# Spannungsversorgung_FinalVersion.net
KiCad netlist of a schematic drawn in EAGLE
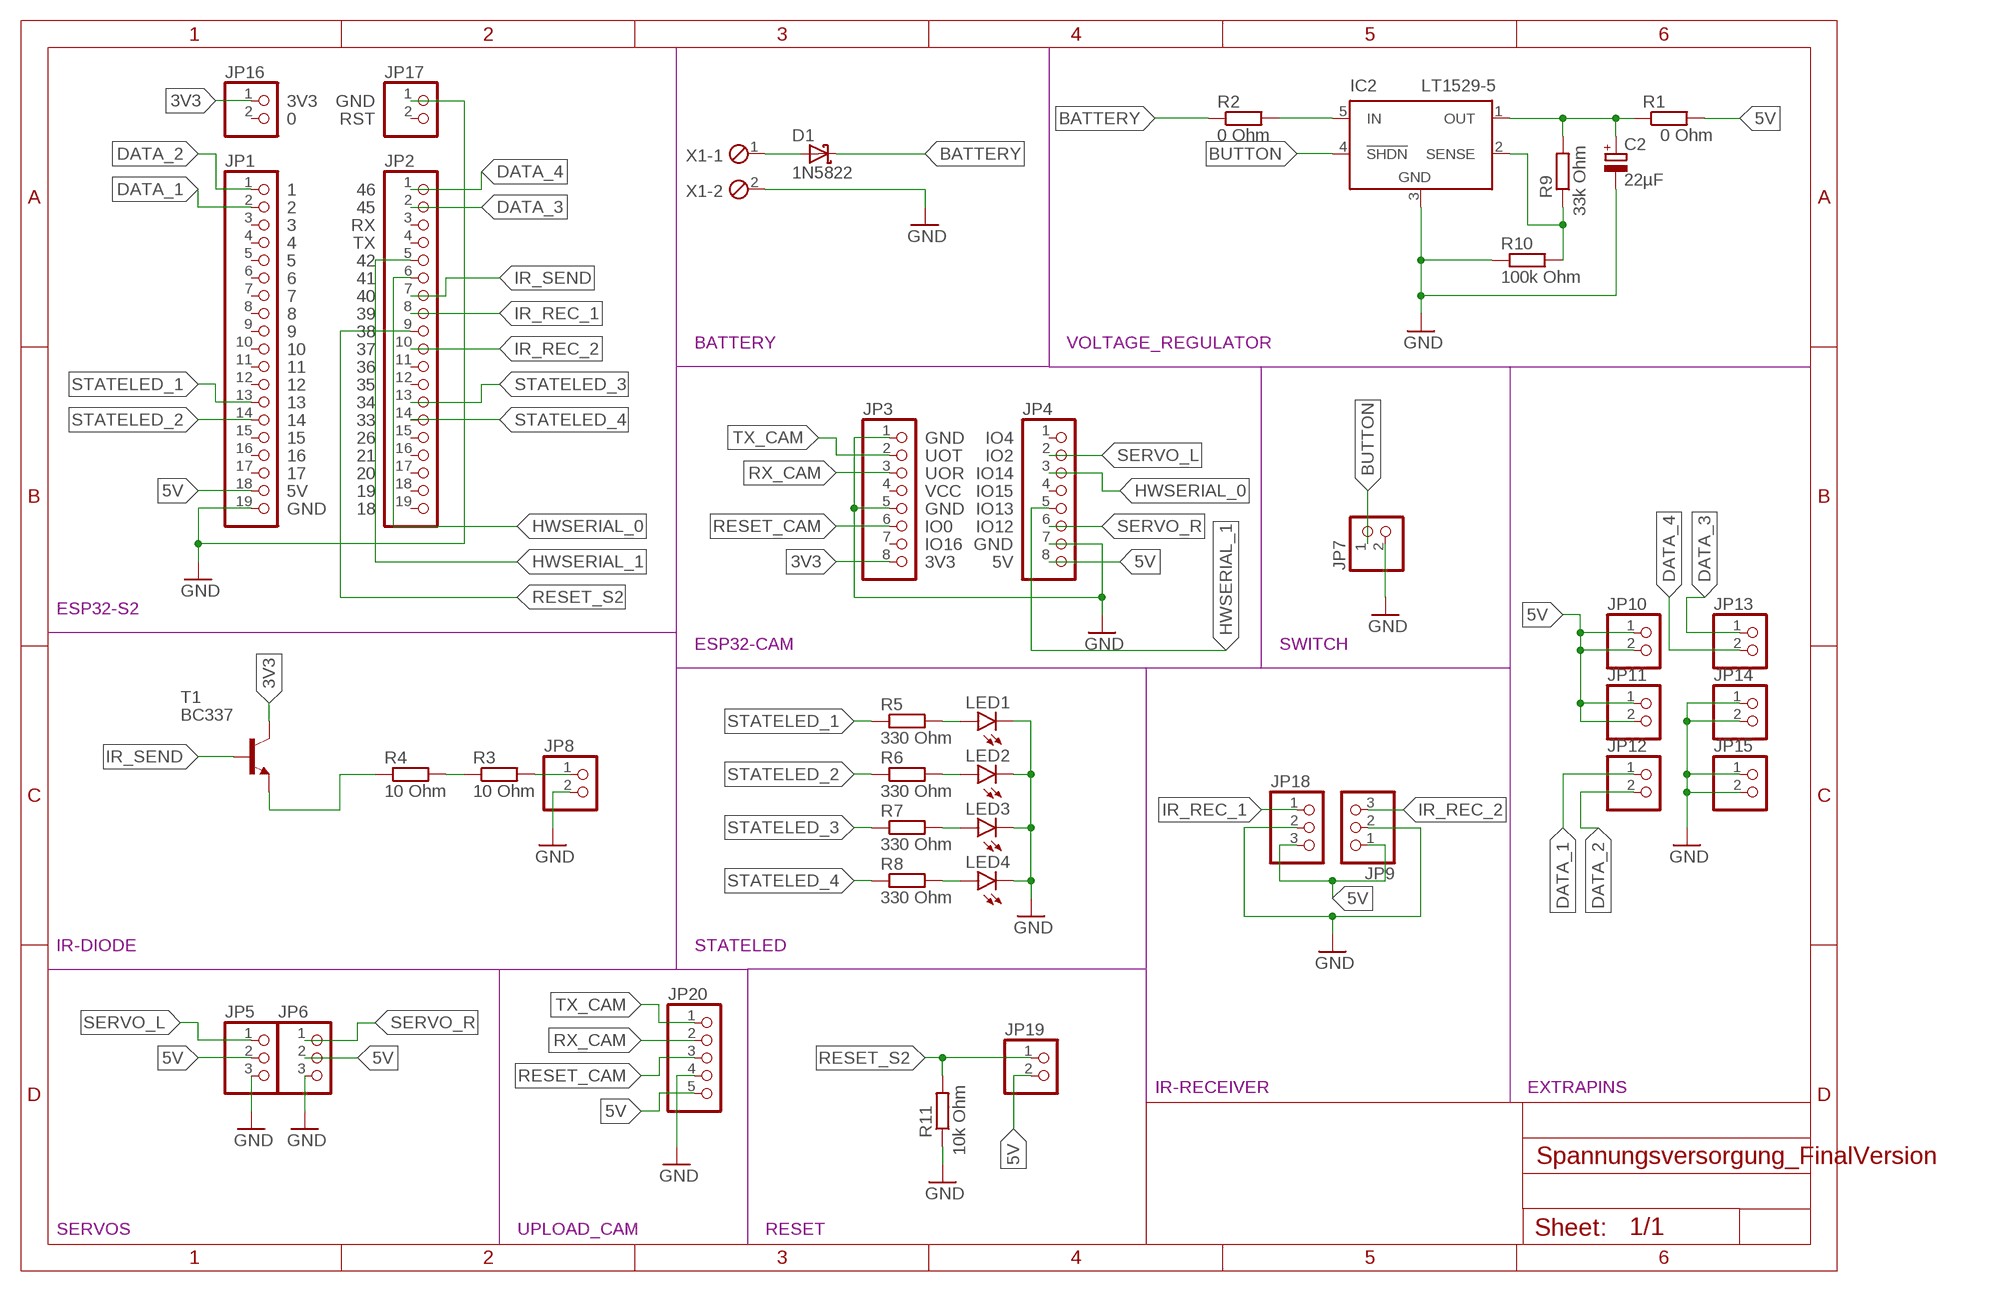
[diagram p0: schematic, sheet 1]

(export (version "E")
  (design (tool "Eeschema 10.0.6"))
  (components
    (comp (ref "C2")
      (value "22µF")
      (footprint "eagle-import:E2,5-5")
      (libsource (lib "eagle-import") (part "CPOL-EUE2.5-5"))
    )
    (comp (ref "D1")
      (value "1N5822")
      (footprint "eagle-import:DIOAD2120W130L950D530P")
      (fields (field (name "MF") "ON Semiconductor"))
      (libsource (lib "eagle-import") (part "1N5822"))
    )
    (comp (ref "IC2")
      (value "LT1529-5")
      (footprint "eagle-import:TO220-5")
      (libsource (lib "eagle-import") (part "LT1529T"))
    )
    (comp (ref "JP1")
      (value "PINHD-1X19")
      (footprint "eagle-import:1X19")
      (libsource (lib "eagle-import") (part "PINHD-1X19"))
    )
    (comp (ref "JP2")
      (value "PINHD-1X19")
      (footprint "eagle-import:1X19")
      (libsource (lib "eagle-import") (part "PINHD-1X19"))
    )
    (comp (ref "JP3")
      (value "PINHD-1X8")
      (footprint "eagle-import:1X08")
      (libsource (lib "eagle-import") (part "PINHD-1X8"))
    )
    (comp (ref "JP4")
      (value "PINHD-1X8")
      (footprint "eagle-import:1X08")
      (libsource (lib "eagle-import") (part "PINHD-1X8"))
    )
    (comp (ref "JP5")
      (value "PINHD-1X3")
      (footprint "eagle-import:1X03")
      (libsource (lib "eagle-import") (part "PINHD-1X3"))
    )
    (comp (ref "JP6")
      (value "PINHD-1X3")
      (footprint "eagle-import:1X03")
      (libsource (lib "eagle-import") (part "PINHD-1X3"))
    )
    (comp (ref "JP7")
      (value "PINHD-1X2")
      (footprint "eagle-import:1X02")
      (libsource (lib "eagle-import") (part "PINHD-1X2"))
    )
    (comp (ref "JP8")
      (value "PINHD-1X2")
      (footprint "eagle-import:1X02")
      (libsource (lib "eagle-import") (part "PINHD-1X2"))
    )
    (comp (ref "JP9")
      (value "PINHD-1X3")
      (footprint "eagle-import:1X03")
      (libsource (lib "eagle-import") (part "PINHD-1X3"))
    )
    (comp (ref "JP10")
      (value "PINHD-1X2")
      (footprint "eagle-import:1X02")
      (libsource (lib "eagle-import") (part "PINHD-1X2"))
    )
    (comp (ref "JP11")
      (value "PINHD-1X2")
      (footprint "eagle-import:1X02")
      (libsource (lib "eagle-import") (part "PINHD-1X2"))
    )
    (comp (ref "JP12")
      (value "PINHD-1X2")
      (footprint "eagle-import:1X02")
      (libsource (lib "eagle-import") (part "PINHD-1X2"))
    )
    (comp (ref "JP13")
      (value "PINHD-1X2")
      (footprint "eagle-import:1X02")
      (libsource (lib "eagle-import") (part "PINHD-1X2"))
    )
    (comp (ref "JP14")
      (value "PINHD-1X2")
      (footprint "eagle-import:1X02")
      (libsource (lib "eagle-import") (part "PINHD-1X2"))
    )
    (comp (ref "JP15")
      (value "PINHD-1X2")
      (footprint "eagle-import:1X02")
      (libsource (lib "eagle-import") (part "PINHD-1X2"))
    )
    (comp (ref "JP16")
      (value "PINHD-1X2")
      (footprint "eagle-import:1X02")
      (libsource (lib "eagle-import") (part "PINHD-1X2"))
    )
    (comp (ref "JP17")
      (value "PINHD-1X2")
      (footprint "eagle-import:1X02")
      (libsource (lib "eagle-import") (part "PINHD-1X2"))
    )
    (comp (ref "JP18")
      (value "PINHD-1X3")
      (footprint "eagle-import:1X03")
      (libsource (lib "eagle-import") (part "PINHD-1X3"))
    )
    (comp (ref "JP19")
      (value "PINHD-1X2")
      (footprint "eagle-import:1X02")
      (libsource (lib "eagle-import") (part "PINHD-1X2"))
    )
    (comp (ref "JP20")
      (value "PINHD-1X5")
      (footprint "eagle-import:1X05")
      (libsource (lib "eagle-import") (part "PINHD-1X5"))
    )
    (comp (ref "LED1")
      (value "LED3MM")
      (footprint "eagle-import:LED3MM")
      (libsource (lib "eagle-import") (part "LED3MM"))
    )
    (comp (ref "LED2")
      (value "LED3MM")
      (footprint "eagle-import:LED3MM")
      (libsource (lib "eagle-import") (part "LED3MM"))
    )
    (comp (ref "LED3")
      (value "LED3MM")
      (footprint "eagle-import:LED3MM")
      (libsource (lib "eagle-import") (part "LED3MM"))
    )
    (comp (ref "LED4")
      (value "LED3MM")
      (footprint "eagle-import:LED3MM")
      (libsource (lib "eagle-import") (part "LED3MM"))
    )
    (comp (ref "R1")
      (value "0 Ohm")
      (footprint "eagle-import:R0805")
      (libsource (lib "eagle-import") (part "R-EU_R0805"))
    )
    (comp (ref "R2")
      (value "0 Ohm")
      (footprint "eagle-import:R0805")
      (libsource (lib "eagle-import") (part "R-EU_R0805"))
    )
    (comp (ref "R3")
      (value "10 Ohm")
      (footprint "eagle-import:0309_12")
      (libsource (lib "eagle-import") (part "R-EU_0309/12"))
    )
    (comp (ref "R4")
      (value "10 Ohm")
      (footprint "eagle-import:0309_12")
      (libsource (lib "eagle-import") (part "R-EU_0309/12"))
    )
    (comp (ref "R5")
      (value "330 Ohm")
      (footprint "eagle-import:R0805")
      (libsource (lib "eagle-import") (part "R-EU_R0805"))
    )
    (comp (ref "R6")
      (value "330 Ohm")
      (footprint "eagle-import:R0805")
      (libsource (lib "eagle-import") (part "R-EU_R0805"))
    )
    (comp (ref "R7")
      (value "330 Ohm")
      (footprint "eagle-import:R0805")
      (libsource (lib "eagle-import") (part "R-EU_R0805"))
    )
    (comp (ref "R8")
      (value "330 Ohm")
      (footprint "eagle-import:R0805")
      (libsource (lib "eagle-import") (part "R-EU_R0805"))
    )
    (comp (ref "R9")
      (value "33k Ohm")
      (footprint "eagle-import:0309_12")
      (libsource (lib "eagle-import") (part "R-EU_0309/12"))
    )
    (comp (ref "R10")
      (value "100k Ohm")
      (footprint "eagle-import:0309_12")
      (libsource (lib "eagle-import") (part "R-EU_0309/12"))
    )
    (comp (ref "R11")
      (value "10k Ohm")
      (footprint "eagle-import:0309_12")
      (libsource (lib "eagle-import") (part "R-EU_0309/12"))
    )
    (comp (ref "T1")
      (value "BC337")
      (footprint "eagle-import:TO92")
      (libsource (lib "eagle-import") (part "BC337"))
    )
    (comp (ref "X1")
      (value "MPT2")
      (footprint "eagle-import:2POL254")
      (libsource (lib "eagle-import") (part "MPT2"))
    )
  )
  (nets
    (net (code "1") (name "3V3") (class "Default")
      (node (ref "JP16") (pin "1") (pinfunction "1_1") (pintype "passive"))
      (node (ref "JP3") (pin "8") (pinfunction "8_8") (pintype "passive"))
      (node (ref "T1") (pin "3") (pinfunction "C_3") (pintype "passive"))
    )
    (net (code "2") (name "5V") (class "Default")
      (node (ref "JP1") (pin "18") (pinfunction "18_18") (pintype "passive"))
      (node (ref "JP10") (pin "1") (pinfunction "1_1") (pintype "passive"))
      (node (ref "JP10") (pin "2") (pinfunction "2_2") (pintype "passive"))
      (node (ref "JP11") (pin "1") (pinfunction "1_1") (pintype "passive"))
      (node (ref "JP11") (pin "2") (pinfunction "2_2") (pintype "passive"))
      (node (ref "JP18") (pin "3") (pinfunction "3_3") (pintype "passive"))
      (node (ref "JP19") (pin "2") (pinfunction "2_2") (pintype "passive"))
      (node (ref "JP20") (pin "5") (pinfunction "5_5") (pintype "passive"))
      (node (ref "JP4") (pin "8") (pinfunction "8_8") (pintype "passive"))
      (node (ref "JP5") (pin "2") (pinfunction "2_2") (pintype "passive"))
      (node (ref "JP6") (pin "2") (pinfunction "2_2") (pintype "passive"))
      (node (ref "JP9") (pin "1") (pinfunction "1_1") (pintype "passive"))
      (node (ref "R1") (pin "2") (pinfunction "2_2") (pintype "passive"))
    )
    (net (code "3") (name "BATTERY") (class "Default")
      (node (ref "D1") (pin "C") (pinfunction "C_C") (pintype "passive"))
      (node (ref "R2") (pin "1") (pinfunction "1_1") (pintype "passive"))
    )
    (net (code "4") (name "BUTTON") (class "Default")
      (node (ref "IC2") (pin "4") (pinfunction "~{SHDN}_4") (pintype "input"))
      (node (ref "JP7") (pin "1") (pinfunction "1_1") (pintype "passive"))
    )
    (net (code "5") (name "DATA_1") (class "Default")
      (node (ref "JP1") (pin "2") (pinfunction "2_2") (pintype "passive"))
      (node (ref "JP12") (pin "1") (pinfunction "1_1") (pintype "passive"))
    )
    (net (code "6") (name "DATA_2") (class "Default")
      (node (ref "JP1") (pin "1") (pinfunction "1_1") (pintype "passive"))
      (node (ref "JP12") (pin "2") (pinfunction "2_2") (pintype "passive"))
    )
    (net (code "7") (name "DATA_3") (class "Default")
      (node (ref "JP13") (pin "1") (pinfunction "1_1") (pintype "passive"))
      (node (ref "JP2") (pin "2") (pinfunction "2_2") (pintype "passive"))
    )
    (net (code "8") (name "DATA_4") (class "Default")
      (node (ref "JP13") (pin "2") (pinfunction "2_2") (pintype "passive"))
      (node (ref "JP2") (pin "1") (pinfunction "1_1") (pintype "passive"))
    )
    (net (code "9") (name "GND") (class "Default")
      (node (ref "C2") (pin "-") (pinfunction "-_-") (pintype "passive"))
      (node (ref "IC2") (pin "3") (pinfunction "GND_3") (pintype "power_in"))
      (node (ref "JP1") (pin "19") (pinfunction "19_19") (pintype "passive"))
      (node (ref "JP14") (pin "1") (pinfunction "1_1") (pintype "passive"))
      (node (ref "JP14") (pin "2") (pinfunction "2_2") (pintype "passive"))
      (node (ref "JP15") (pin "1") (pinfunction "1_1") (pintype "passive"))
      (node (ref "JP15") (pin "2") (pinfunction "2_2") (pintype "passive"))
      (node (ref "JP17") (pin "1") (pinfunction "1_1") (pintype "passive"))
      (node (ref "JP18") (pin "2") (pinfunction "2_2") (pintype "passive"))
      (node (ref "JP20") (pin "4") (pinfunction "4_4") (pintype "passive"))
      (node (ref "JP3") (pin "1") (pinfunction "1_1") (pintype "passive"))
      (node (ref "JP3") (pin "5") (pinfunction "5_5") (pintype "passive"))
      (node (ref "JP4") (pin "7") (pinfunction "7_7") (pintype "passive"))
      (node (ref "JP5") (pin "3") (pinfunction "3_3") (pintype "passive"))
      (node (ref "JP6") (pin "3") (pinfunction "3_3") (pintype "passive"))
      (node (ref "JP7") (pin "2") (pinfunction "2_2") (pintype "passive"))
      (node (ref "JP8") (pin "2") (pinfunction "2_2") (pintype "passive"))
      (node (ref "JP9") (pin "2") (pinfunction "2_2") (pintype "passive"))
      (node (ref "LED1") (pin "K") (pinfunction "C_K") (pintype "passive"))
      (node (ref "LED2") (pin "K") (pinfunction "C_K") (pintype "passive"))
      (node (ref "LED3") (pin "K") (pinfunction "C_K") (pintype "passive"))
      (node (ref "LED4") (pin "K") (pinfunction "C_K") (pintype "passive"))
      (node (ref "R10") (pin "1") (pinfunction "1_1") (pintype "passive"))
      (node (ref "R11") (pin "1") (pinfunction "1_1") (pintype "passive"))
      (node (ref "X1") (pin "2") (pinfunction "1_2") (pintype "passive"))
    )
    (net (code "10") (name "HWSERIAL_0") (class "Default")
      (node (ref "JP2") (pin "6") (pinfunction "6_6") (pintype "passive"))
      (node (ref "JP4") (pin "3") (pinfunction "3_3") (pintype "passive"))
    )
    (net (code "11") (name "HWSERIAL_1") (class "Default")
      (node (ref "JP2") (pin "5") (pinfunction "5_5") (pintype "passive"))
      (node (ref "JP4") (pin "5") (pinfunction "5_5") (pintype "passive"))
    )
    (net (code "12") (name "IR_REC_1") (class "Default")
      (node (ref "JP18") (pin "1") (pinfunction "1_1") (pintype "passive"))
      (node (ref "JP2") (pin "8") (pinfunction "8_8") (pintype "passive"))
    )
    (net (code "13") (name "IR_REC_2") (class "Default")
      (node (ref "JP2") (pin "10") (pinfunction "10_10") (pintype "passive"))
      (node (ref "JP9") (pin "3") (pinfunction "3_3") (pintype "passive"))
    )
    (net (code "14") (name "IR_SEND") (class "Default")
      (node (ref "JP2") (pin "7") (pinfunction "7_7") (pintype "passive"))
      (node (ref "T1") (pin "2") (pinfunction "B_2") (pintype "passive"))
    )
    (net (code "15") (name "Net-(D1-PadA)") (class "Default")
      (node (ref "D1") (pin "A") (pinfunction "A_A") (pintype "passive"))
      (node (ref "X1") (pin "1") (pinfunction "1_1") (pintype "passive"))
    )
    (net (code "16") (name "Net-(IC2-IN)") (class "Default")
      (node (ref "IC2") (pin "5") (pinfunction "IN_5") (pintype "input"))
      (node (ref "R2") (pin "2") (pinfunction "2_2") (pintype "passive"))
    )
    (net (code "17") (name "Net-(IC2-OUT)") (class "Default")
      (node (ref "C2") (pin "+") (pinfunction "+_+") (pintype "passive"))
      (node (ref "IC2") (pin "1") (pinfunction "OUT_1") (pintype "output"))
      (node (ref "R1") (pin "1") (pinfunction "1_1") (pintype "passive"))
      (node (ref "R9") (pin "2") (pinfunction "2_2") (pintype "passive"))
    )
    (net (code "18") (name "Net-(IC2-SENSE)") (class "Default")
      (node (ref "IC2") (pin "2") (pinfunction "SENSE_2") (pintype "input"))
      (node (ref "R10") (pin "2") (pinfunction "2_2") (pintype "passive"))
      (node (ref "R9") (pin "1") (pinfunction "1_1") (pintype "passive"))
    )
    (net (code "19") (name "Net-(JP8-Pad1)") (class "Default")
      (node (ref "JP8") (pin "1") (pinfunction "1_1") (pintype "passive"))
      (node (ref "R3") (pin "2") (pinfunction "2_2") (pintype "passive"))
    )
    (net (code "20") (name "Net-(LED1-PadA)") (class "Default")
      (node (ref "LED1") (pin "A") (pinfunction "A_A") (pintype "passive"))
      (node (ref "R5") (pin "2") (pinfunction "2_2") (pintype "passive"))
    )
    (net (code "21") (name "Net-(LED2-PadA)") (class "Default")
      (node (ref "LED2") (pin "A") (pinfunction "A_A") (pintype "passive"))
      (node (ref "R6") (pin "2") (pinfunction "2_2") (pintype "passive"))
    )
    (net (code "22") (name "Net-(LED3-PadA)") (class "Default")
      (node (ref "LED3") (pin "A") (pinfunction "A_A") (pintype "passive"))
      (node (ref "R7") (pin "2") (pinfunction "2_2") (pintype "passive"))
    )
    (net (code "23") (name "Net-(LED4-PadA)") (class "Default")
      (node (ref "LED4") (pin "A") (pinfunction "A_A") (pintype "passive"))
      (node (ref "R8") (pin "2") (pinfunction "2_2") (pintype "passive"))
    )
    (net (code "24") (name "Net-(R3-Pad1)") (class "Default")
      (node (ref "R3") (pin "1") (pinfunction "1_1") (pintype "passive"))
      (node (ref "R4") (pin "2") (pinfunction "2_2") (pintype "passive"))
    )
    (net (code "25") (name "Net-(T1-E)") (class "Default")
      (node (ref "R4") (pin "1") (pinfunction "1_1") (pintype "passive"))
      (node (ref "T1") (pin "1") (pinfunction "E_1") (pintype "passive"))
    )
    (net (code "26") (name "RESET_CAM") (class "Default")
      (node (ref "JP20") (pin "3") (pinfunction "3_3") (pintype "passive"))
      (node (ref "JP3") (pin "6") (pinfunction "6_6") (pintype "passive"))
    )
    (net (code "27") (name "RESET_S2") (class "Default")
      (node (ref "JP19") (pin "1") (pinfunction "1_1") (pintype "passive"))
      (node (ref "JP2") (pin "9") (pinfunction "9_9") (pintype "passive"))
      (node (ref "R11") (pin "2") (pinfunction "2_2") (pintype "passive"))
    )
    (net (code "28") (name "RX_CAM") (class "Default")
      (node (ref "JP20") (pin "2") (pinfunction "2_2") (pintype "passive"))
      (node (ref "JP3") (pin "3") (pinfunction "3_3") (pintype "passive"))
    )
    (net (code "29") (name "SERVO_L") (class "Default")
      (node (ref "JP4") (pin "2") (pinfunction "2_2") (pintype "passive"))
      (node (ref "JP5") (pin "1") (pinfunction "1_1") (pintype "passive"))
    )
    (net (code "30") (name "SERVO_R") (class "Default")
      (node (ref "JP4") (pin "6") (pinfunction "6_6") (pintype "passive"))
      (node (ref "JP6") (pin "1") (pinfunction "1_1") (pintype "passive"))
    )
    (net (code "31") (name "STATELED_1") (class "Default")
      (node (ref "JP1") (pin "13") (pinfunction "13_13") (pintype "passive"))
      (node (ref "R5") (pin "1") (pinfunction "1_1") (pintype "passive"))
    )
    (net (code "32") (name "STATELED_2") (class "Default")
      (node (ref "JP1") (pin "14") (pinfunction "14_14") (pintype "passive"))
      (node (ref "R6") (pin "1") (pinfunction "1_1") (pintype "passive"))
    )
    (net (code "33") (name "STATELED_3") (class "Default")
      (node (ref "JP2") (pin "13") (pinfunction "13_13") (pintype "passive"))
      (node (ref "R7") (pin "1") (pinfunction "1_1") (pintype "passive"))
    )
    (net (code "34") (name "STATELED_4") (class "Default")
      (node (ref "JP2") (pin "14") (pinfunction "14_14") (pintype "passive"))
      (node (ref "R8") (pin "1") (pinfunction "1_1") (pintype "passive"))
    )
    (net (code "35") (name "TX_CAM") (class "Default")
      (node (ref "JP20") (pin "1") (pinfunction "1_1") (pintype "passive"))
      (node (ref "JP3") (pin "2") (pinfunction "2_2") (pintype "passive"))
    )
    (net (code "36") (name "unconnected-(JP1-Pad3)") (class "Default")
      (node (ref "JP1") (pin "3") (pinfunction "3_3") (pintype "passive"))
    )
    (net (code "37") (name "unconnected-(JP1-Pad4)") (class "Default")
      (node (ref "JP1") (pin "4") (pinfunction "4_4") (pintype "passive"))
    )
    (net (code "38") (name "unconnected-(JP1-Pad5)") (class "Default")
      (node (ref "JP1") (pin "5") (pinfunction "5_5") (pintype "passive"))
    )
    (net (code "39") (name "unconnected-(JP1-Pad6)") (class "Default")
      (node (ref "JP1") (pin "6") (pinfunction "6_6") (pintype "passive"))
    )
    (net (code "40") (name "unconnected-(JP1-Pad7)") (class "Default")
      (node (ref "JP1") (pin "7") (pinfunction "7_7") (pintype "passive"))
    )
    (net (code "41") (name "unconnected-(JP1-Pad8)") (class "Default")
      (node (ref "JP1") (pin "8") (pinfunction "8_8") (pintype "passive"))
    )
    (net (code "42") (name "unconnected-(JP1-Pad9)") (class "Default")
      (node (ref "JP1") (pin "9") (pinfunction "9_9") (pintype "passive"))
    )
    (net (code "43") (name "unconnected-(JP1-Pad10)") (class "Default")
      (node (ref "JP1") (pin "10") (pinfunction "10_10") (pintype "passive"))
    )
    (net (code "44") (name "unconnected-(JP1-Pad11)") (class "Default")
      (node (ref "JP1") (pin "11") (pinfunction "11_11") (pintype "passive"))
    )
    (net (code "45") (name "unconnected-(JP1-Pad12)") (class "Default")
      (node (ref "JP1") (pin "12") (pinfunction "12_12") (pintype "passive"))
    )
    (net (code "46") (name "unconnected-(JP1-Pad15)") (class "Default")
      (node (ref "JP1") (pin "15") (pinfunction "15_15") (pintype "passive"))
    )
    (net (code "47") (name "unconnected-(JP1-Pad16)") (class "Default")
      (node (ref "JP1") (pin "16") (pinfunction "16_16") (pintype "passive"))
    )
    (net (code "48") (name "unconnected-(JP1-Pad17)") (class "Default")
      (node (ref "JP1") (pin "17") (pinfunction "17_17") (pintype "passive"))
    )
    (net (code "49") (name "unconnected-(JP2-Pad3)") (class "Default")
      (node (ref "JP2") (pin "3") (pinfunction "3_3") (pintype "passive"))
    )
    (net (code "50") (name "unconnected-(JP2-Pad4)") (class "Default")
      (node (ref "JP2") (pin "4") (pinfunction "4_4") (pintype "passive"))
    )
    (net (code "51") (name "unconnected-(JP2-Pad11)") (class "Default")
      (node (ref "JP2") (pin "11") (pinfunction "11_11") (pintype "passive"))
    )
    (net (code "52") (name "unconnected-(JP2-Pad12)") (class "Default")
      (node (ref "JP2") (pin "12") (pinfunction "12_12") (pintype "passive"))
    )
    (net (code "53") (name "unconnected-(JP2-Pad15)") (class "Default")
      (node (ref "JP2") (pin "15") (pinfunction "15_15") (pintype "passive"))
    )
    (net (code "54") (name "unconnected-(JP2-Pad16)") (class "Default")
      (node (ref "JP2") (pin "16") (pinfunction "16_16") (pintype "passive"))
    )
    (net (code "55") (name "unconnected-(JP2-Pad17)") (class "Default")
      (node (ref "JP2") (pin "17") (pinfunction "17_17") (pintype "passive"))
    )
    (net (code "56") (name "unconnected-(JP2-Pad18)") (class "Default")
      (node (ref "JP2") (pin "18") (pinfunction "18_18") (pintype "passive"))
    )
    (net (code "57") (name "unconnected-(JP2-Pad19)") (class "Default")
      (node (ref "JP2") (pin "19") (pinfunction "19_19") (pintype "passive"))
    )
    (net (code "58") (name "unconnected-(JP3-Pad4)") (class "Default")
      (node (ref "JP3") (pin "4") (pinfunction "4_4") (pintype "passive"))
    )
    (net (code "59") (name "unconnected-(JP3-Pad7)") (class "Default")
      (node (ref "JP3") (pin "7") (pinfunction "7_7") (pintype "passive"))
    )
    (net (code "60") (name "unconnected-(JP4-Pad1)") (class "Default")
      (node (ref "JP4") (pin "1") (pinfunction "1_1") (pintype "passive"))
    )
    (net (code "61") (name "unconnected-(JP4-Pad4)") (class "Default")
      (node (ref "JP4") (pin "4") (pinfunction "4_4") (pintype "passive"))
    )
    (net (code "62") (name "unconnected-(JP16-Pad2)") (class "Default")
      (node (ref "JP16") (pin "2") (pinfunction "2_2") (pintype "passive"))
    )
    (net (code "63") (name "unconnected-(JP17-Pad2)") (class "Default")
      (node (ref "JP17") (pin "2") (pinfunction "2_2") (pintype "passive"))
    )
  )
)
